# Buck_Schematic.net
KiCad netlist of a schematic drawn in Altium Designer
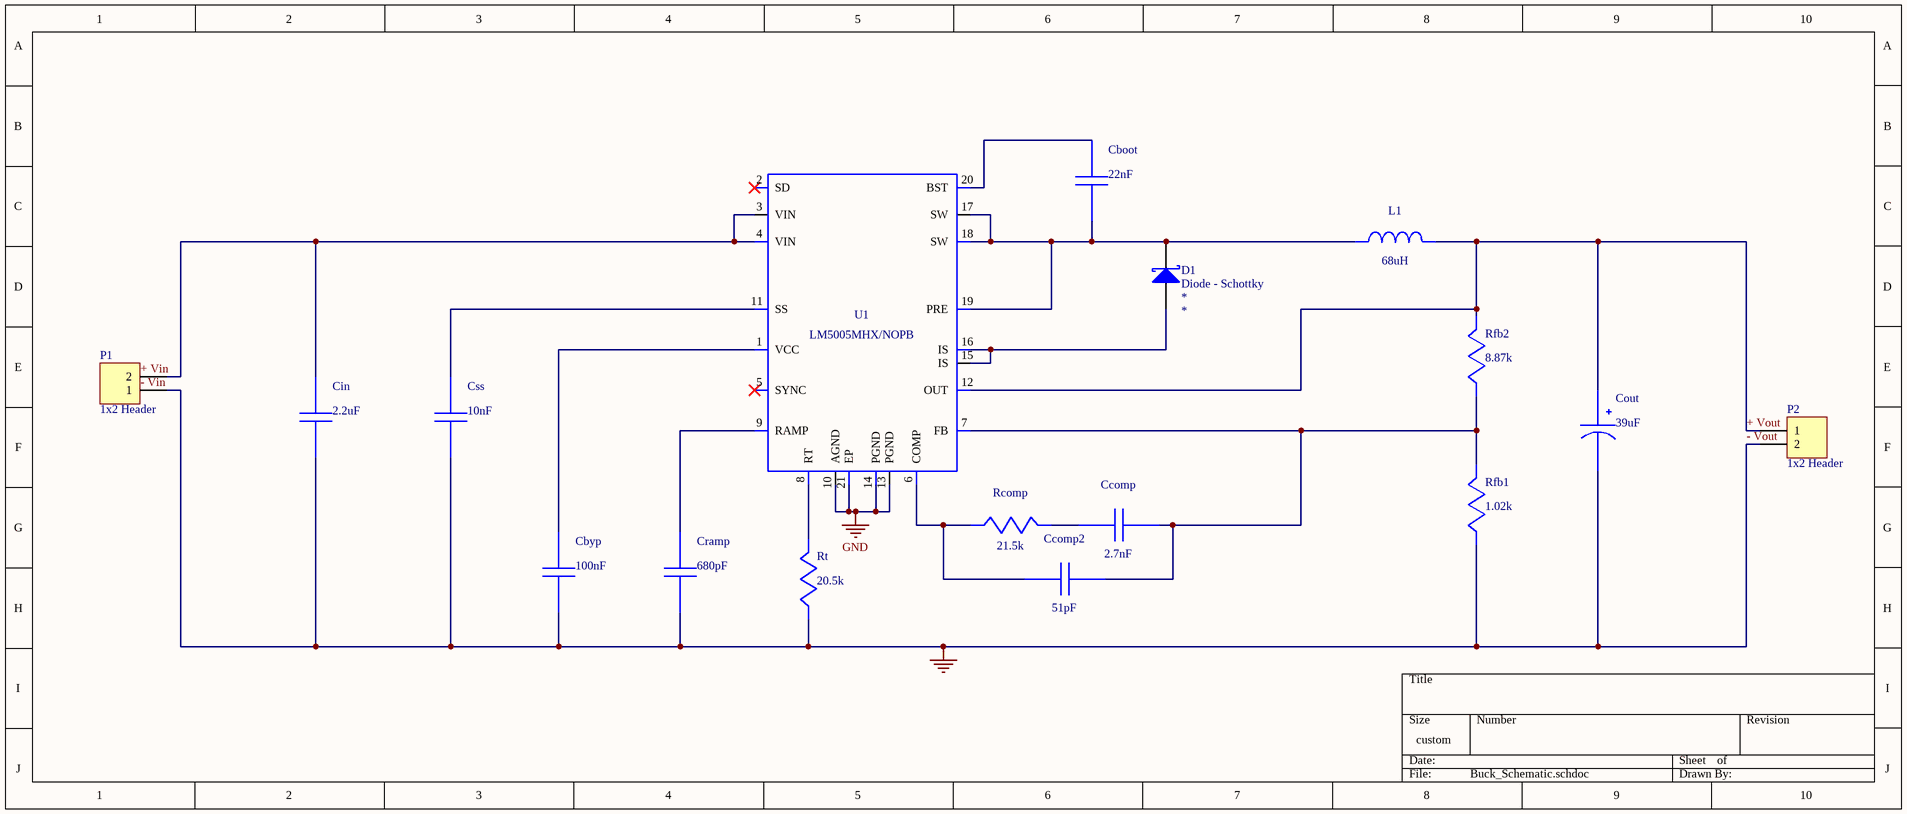
[diagram p0: Buck_Schematic.schdoc]

(export (version "E")
  (design (tool "Eeschema 10.0.6"))
  (components
    (comp (ref "Cboot")
      (value "22nF")
      (footprint "0805 - Capacitor")
      (description "C0805C223K5RACTU")
      (libsource (lib "TI WEBENCH") (part "Cboot"))
    )
    (comp (ref "Cbyp")
      (value "100nF")
      (footprint "0805 - Capacitor")
      (description "C0805C104M5RACTU")
      (libsource (lib "TI WEBENCH") (part "Cbyp"))
    )
    (comp (ref "Ccomp")
      (value "2.7nF")
      (description "GRM033R71C272KA8")
      (fields (field (name "MANUFACTURER PART NUMBER") "GRM033R71C272KA88D"))
      (libsource (lib "TI WEBENCH") (part "Ccomp"))
    )
    (comp (ref "Ccomp2")
      (value "51pF")
      (footprint "0805 - Capacitor")
      (description "CL21C510JBANNNC")
      (libsource (lib "TI WEBENCH") (part "Ccomp2"))
    )
    (comp (ref "Cin")
      (value "2.2uF")
      (footprint "1210 - Capacitor")
      (description "C3225X7R2A225K23")
      (fields (field (name "MANUFACTURER PART NUMBER") "C3225X7R2A225K230AB"))
      (libsource (lib "TI WEBENCH") (part "Cin"))
    )
    (comp (ref "Cout") (value "39uF") (description "16SVPC39MV") (libsource (lib "TI WEBENCH") (part "Cout")))
    (comp (ref "Cramp")
      (value "680pF")
      (footprint "0603 - Capacitor")
      (description "C0603C681K5RACTU")
      (libsource (lib "TI WEBENCH") (part "Cramp"))
    )
    (comp (ref "Css")
      (value "10nF")
      (footprint "0805 - Capacitor")
      (description "CC0805KRX7R9BB10")
      (fields (field (name "MANUFACTURER PART NUMBER") "CC0805KRX7R9BB103"))
      (libsource (lib "TI WEBENCH") (part "Css"))
    )
    (comp (ref "D1")
      (value "Diode - Schottky")
      (description "Schottky Rectifier")
      (fields (field (name "ALTIUM_VALUE") "*") (field (name "MANUFACTURER PART NUMBER") "*"))
      (libsource (lib "General") (part "Diode - Schottky"))
    )
    (comp (ref "L1")
      (value "68uH")
      (footprint "MSS1210 - INDUCTOR")
      (description "Unknown")
      (fields (field (name "MANUFACTURER PART NUMBER") "MSS1210-683MEB"))
      (libsource (lib "TI WEBENCH") (part "L1"))
    )
    (comp (ref "P1")
      (value "1x2 Header")
      (footprint "HDR1X2")
      (description "1x2 Pin Header")
      (libsource (lib "") (part "1x2 Header_1"))
    )
    (comp (ref "P2")
      (value "1x2 Header")
      (footprint "HDR1X2")
      (description "1x2 Pin Header")
      (libsource (lib "GeneralConnectors") (part "1x2 Header"))
    )
    (comp (ref "Rcomp")
      (value "21.5k")
      (footprint "0603 - Resistor")
      (description "CRCW060321K5FKEA")
      (libsource (lib "TI WEBENCH") (part "Rcomp"))
    )
    (comp (ref "Rfb1")
      (value "1.02k")
      (footprint "0805 - Resistor")
      (description "ERJ-6ENF1021V")
      (libsource (lib "TI WEBENCH") (part "Rfb1"))
    )
    (comp (ref "Rfb2")
      (value "8.87k")
      (footprint "0805 - Resistor")
      (description "ERJ-6ENF8871V")
      (libsource (lib "TI WEBENCH") (part "Rfb2"))
    )
    (comp (ref "Rt")
      (value "20.5k")
      (footprint "0603 - Resistor")
      (description "CRCW060320K5FKEA")
      (libsource (lib "TI WEBENCH") (part "Rt"))
    )
    (comp (ref "U1")
      (value "LM5005MHX/NOPB")
      (footprint "LM5005")
      (fields (field (name "PACKAGEREFERENCE") "LM5005MHX/NOPB"))
      (libsource (lib "TI WEBENCH") (part "U1"))
    )
  )
  (nets
    (net (code "2") (name "/+ Vout") (class "Default")
      (node (ref "Cout") (pin "1") (pinfunction "+_1") (pintype "passive"))
      (node (ref "L1") (pin "2") (pinfunction "2_2") (pintype "passive"))
      (node (ref "P2") (pin "1") (pinfunction "1_1") (pintype "passive"))
      (node (ref "Rfb2") (pin "1") (pinfunction "1_1") (pintype "passive"))
      (node (ref "U1") (pin "12") (pinfunction "OUT_12") (pintype "passive"))
    )
    (net (code "4") (name "0") (class "Default")
      (node (ref "Cbyp") (pin "2") (pinfunction "2_2") (pintype "passive"))
      (node (ref "Cin") (pin "2") (pinfunction "2_2") (pintype "passive"))
      (node (ref "Cout") (pin "2") (pinfunction "-_2") (pintype "passive"))
      (node (ref "Cramp") (pin "2") (pinfunction "2_2") (pintype "passive"))
      (node (ref "Css") (pin "2") (pinfunction "2_2") (pintype "passive"))
      (node (ref "P1") (pin "1") (pinfunction "1_1") (pintype "passive"))
      (node (ref "P2") (pin "2") (pinfunction "2_2") (pintype "passive"))
      (node (ref "Rfb1") (pin "2") (pinfunction "2_2") (pintype "passive"))
      (node (ref "Rt") (pin "2") (pinfunction "2_2") (pintype "passive"))
    )
    (net (code "5") (name "GND") (class "Default")
      (node (ref "U1") (pin "10") (pinfunction "AGND_10") (pintype "passive"))
      (node (ref "U1") (pin "13") (pinfunction "PGND_13") (pintype "passive"))
      (node (ref "U1") (pin "14") (pinfunction "PGND_14") (pintype "passive"))
      (node (ref "U1") (pin "21") (pinfunction "EP_21") (pintype "passive"))
    )
    (net (code "6") (name "Net-(Ccomp-Pad2)") (class "Default")
      (node (ref "Ccomp") (pin "2") (pinfunction "2_2") (pintype "passive"))
      (node (ref "Rcomp") (pin "1") (pinfunction "1_1") (pintype "passive"))
    )
    (net (code "7") (name "Net-(Cin-Pad1)") (class "Default")
      (node (ref "Cin") (pin "1") (pinfunction "1_1") (pintype "passive"))
      (node (ref "P1") (pin "2") (pinfunction "2_2") (pintype "passive"))
      (node (ref "U1") (pin "3") (pinfunction "VIN_3") (pintype "passive"))
      (node (ref "U1") (pin "4") (pinfunction "VIN_4") (pintype "passive"))
    )
    (net (code "8") (name "Net-(D1-A)") (class "Default")
      (node (ref "D1") (pin "3") (pinfunction "A_3") (pintype "passive"))
      (node (ref "U1") (pin "15") (pinfunction "IS_15") (pintype "passive"))
      (node (ref "U1") (pin "16") (pinfunction "IS_16") (pintype "passive"))
    )
    (net (code "9") (name "Net-(D1-K)") (class "Default")
      (node (ref "Cboot") (pin "2") (pinfunction "2_2") (pintype "passive"))
      (node (ref "D1") (pin "1") (pinfunction "K_1") (pintype "passive"))
      (node (ref "L1") (pin "1") (pinfunction "1_1") (pintype "passive"))
      (node (ref "U1") (pin "17") (pinfunction "SW_17") (pintype "passive"))
      (node (ref "U1") (pin "18") (pinfunction "SW_18") (pintype "passive"))
      (node (ref "U1") (pin "19") (pinfunction "PRE_19") (pintype "passive"))
    )
    (net (code "10") (name "Net-(U1-BST)") (class "Default")
      (node (ref "Cboot") (pin "1") (pinfunction "1_1") (pintype "passive"))
      (node (ref "U1") (pin "20") (pinfunction "BST_20") (pintype "passive"))
    )
    (net (code "11") (name "Net-(U1-COMP)") (class "Default")
      (node (ref "Ccomp2") (pin "2") (pinfunction "2_2") (pintype "passive"))
      (node (ref "Rcomp") (pin "2") (pinfunction "2_2") (pintype "passive"))
      (node (ref "U1") (pin "6") (pinfunction "COMP_6") (pintype "passive"))
    )
    (net (code "12") (name "Net-(U1-FB)") (class "Default")
      (node (ref "Ccomp") (pin "1") (pinfunction "1_1") (pintype "passive"))
      (node (ref "Ccomp2") (pin "1") (pinfunction "1_1") (pintype "passive"))
      (node (ref "Rfb1") (pin "1") (pinfunction "1_1") (pintype "passive"))
      (node (ref "Rfb2") (pin "2") (pinfunction "2_2") (pintype "passive"))
      (node (ref "U1") (pin "7") (pinfunction "FB_7") (pintype "passive"))
    )
    (net (code "13") (name "Net-(U1-RAMP)") (class "Default")
      (node (ref "Cramp") (pin "1") (pinfunction "1_1") (pintype "passive"))
      (node (ref "U1") (pin "9") (pinfunction "RAMP_9") (pintype "passive"))
    )
    (net (code "14") (name "Net-(U1-RT)") (class "Default")
      (node (ref "Rt") (pin "1") (pinfunction "1_1") (pintype "passive"))
      (node (ref "U1") (pin "8") (pinfunction "RT_8") (pintype "passive"))
    )
    (net (code "15") (name "Net-(U1-SS)") (class "Default")
      (node (ref "Css") (pin "1") (pinfunction "1_1") (pintype "passive"))
      (node (ref "U1") (pin "11") (pinfunction "SS_11") (pintype "passive"))
    )
    (net (code "16") (name "Net-(U1-VCC)") (class "Default")
      (node (ref "Cbyp") (pin "1") (pinfunction "1_1") (pintype "passive"))
      (node (ref "U1") (pin "1") (pinfunction "VCC_1") (pintype "passive"))
    )
    (net (code "17") (name "unconnected-(U1-SD-Pad2)") (class "Default")
      (node (ref "U1") (pin "2") (pinfunction "SD_2") (pintype "passive+no_connect"))
    )
    (net (code "18") (name "unconnected-(U1-SYNC-Pad5)") (class "Default")
      (node (ref "U1") (pin "5") (pinfunction "SYNC_5") (pintype "passive+no_connect"))
    )
  )
)
